# MCU.net
KiCad netlist of a schematic drawn in Altium Designer
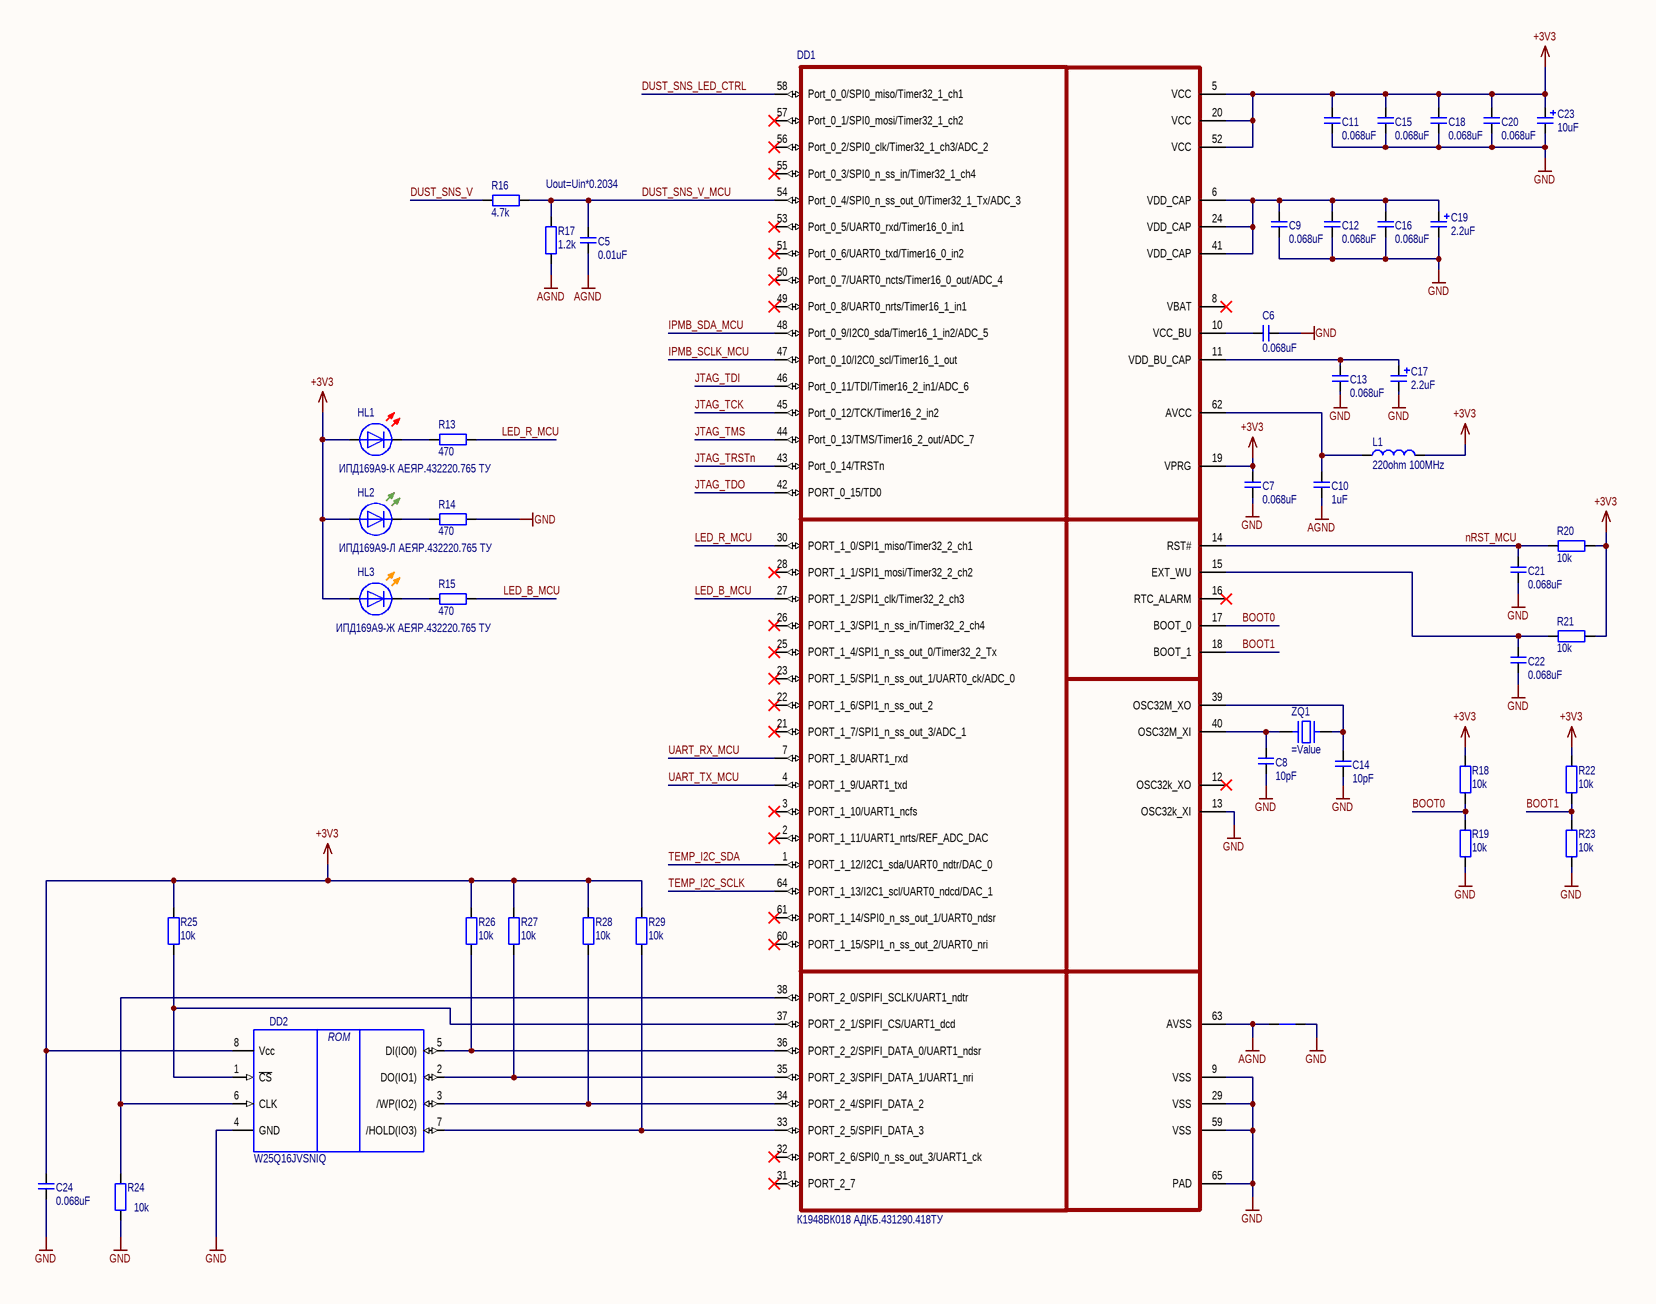
[diagram p0: MCU.SchDoc]

(export (version "E")
  (design (tool "Eeschema 10.0.6"))
  (components
    (comp (ref "C5")
      (value "0.01uF")
      (footprint "CAP 0603_1608")
      (description "Конденсатор К10-83 - 50 В - 0,01 мкФ ±20 % - Н20 - N - 1 АЖЯР.673511.008 ТУ")
      (fields
        (field (name "MANUFACTURER PART NUMBER") "К10-83 - 50 В - 0,01 мкФ ±20 % - Н20 - N - 1 АЖЯР.673511.008 ТУ")
        (field (name "TOLERANCE") "± 20%")
      )
      (libsource (lib "ComponentsDb") (part "Capacitor_Unpolar"))
    )
    (comp (ref "C6")
      (value "0.068uF")
      (footprint "CAP 0603_1608")
      (description "Конденсатор К10-83 - 10 В - 0,068 мкФ ±20 % - Н20 - N - 1 АЖЯР.673511.008 ТУ")
      (fields
        (field (name "MANUFACTURER PART NUMBER") "К10-83 - 10 В - 0,068 мкФ ±20 % - Н20 - N - 1 АЖЯР.673511.008 ТУ")
        (field (name "TOLERANCE") "± 20%")
      )
      (libsource (lib "ComponentsDb") (part "Capacitor_Unpolar"))
    )
    (comp (ref "C7")
      (value "0.068uF")
      (footprint "CAP 0603_1608")
      (description "Конденсатор К10-83 - 10 В - 0,068 мкФ ±20 % - Н20 - N - 1 АЖЯР.673511.008 ТУ")
      (fields
        (field (name "MANUFACTURER PART NUMBER") "К10-83 - 10 В - 0,068 мкФ ±20 % - Н20 - N - 1 АЖЯР.673511.008 ТУ")
        (field (name "TOLERANCE") "± 20%")
      )
      (libsource (lib "ComponentsDb") (part "Capacitor_Unpolar"))
    )
    (comp (ref "C8")
      (value "10pF")
      (footprint "CAP 0603_1608")
      (description "Конденсатор К10-83 - 50 В - 10 пФ ±10 % - МП0 - N - 1 АЖЯР.673511.008 ТУ")
      (fields
        (field (name "MANUFACTURER PART NUMBER") "К10-83 - 50 В - 10 пФ ±10 % - МП0 - N - 1 АЖЯР.673511.008 ТУ")
        (field (name "TOLERANCE") "± 10%")
      )
      (libsource (lib "ComponentsDb") (part "Capacitor_Unpolar"))
    )
    (comp (ref "C9")
      (value "0.068uF")
      (footprint "CAP 0603_1608")
      (description "Конденсатор К10-83 - 10 В - 0,068 мкФ ±20 % - Н20 - N - 1 АЖЯР.673511.008 ТУ")
      (fields
        (field (name "MANUFACTURER PART NUMBER") "К10-83 - 10 В - 0,068 мкФ ±20 % - Н20 - N - 1 АЖЯР.673511.008 ТУ")
        (field (name "TOLERANCE") "± 20%")
      )
      (libsource (lib "ComponentsDb") (part "Capacitor_Unpolar"))
    )
    (comp (ref "C10")
      (value "1uF")
      (footprint "CAP 1210_3225 - 1.8MM")
      (description "Конденсатор К10-83 - 16 В - 1 мкФ ±20 % - Н20 - N - 1 АЖЯР.673511.008 ТУ")
      (fields
        (field (name "MANUFACTURER PART NUMBER") "К10-83 - 16 В - 1 мкФ ±20 % - Н20 - N - 1 АЖЯР.673511.008 ТУ")
        (field (name "TOLERANCE") "± 20%")
      )
      (libsource (lib "ComponentsDb") (part "Capacitor_Unpolar"))
    )
    (comp (ref "C11")
      (value "0.068uF")
      (footprint "CAP 0603_1608")
      (description "Конденсатор К10-83 - 10 В - 0,068 мкФ ±20 % - Н20 - N - 1 АЖЯР.673511.008 ТУ")
      (fields
        (field (name "MANUFACTURER PART NUMBER") "К10-83 - 10 В - 0,068 мкФ ±20 % - Н20 - N - 1 АЖЯР.673511.008 ТУ")
        (field (name "TOLERANCE") "± 20%")
      )
      (libsource (lib "") (part "Capacitor_Unpolar_1"))
    )
    (comp (ref "C12")
      (value "0.068uF")
      (footprint "CAP 0603_1608")
      (description "Конденсатор К10-83 - 10 В - 0,068 мкФ ±20 % - Н20 - N - 1 АЖЯР.673511.008 ТУ")
      (fields
        (field (name "MANUFACTURER PART NUMBER") "К10-83 - 10 В - 0,068 мкФ ±20 % - Н20 - N - 1 АЖЯР.673511.008 ТУ")
        (field (name "TOLERANCE") "± 20%")
      )
      (libsource (lib "ComponentsDb") (part "Capacitor_Unpolar"))
    )
    (comp (ref "C13")
      (value "0.068uF")
      (footprint "CAP 0603_1608")
      (description "Конденсатор К10-83 - 10 В - 0,068 мкФ ±20 % - Н20 - N - 1 АЖЯР.673511.008 ТУ")
      (fields
        (field (name "MANUFACTURER PART NUMBER") "К10-83 - 10 В - 0,068 мкФ ±20 % - Н20 - N - 1 АЖЯР.673511.008 ТУ")
        (field (name "TOLERANCE") "± 20%")
      )
      (libsource (lib "ComponentsDb") (part "Capacitor_Unpolar"))
    )
    (comp (ref "C14")
      (value "10pF")
      (footprint "CAP 0603_1608")
      (description "Конденсатор К10-83 - 50 В - 10 пФ ±10 % - МП0 - N - 1 АЖЯР.673511.008 ТУ")
      (fields
        (field (name "MANUFACTURER PART NUMBER") "К10-83 - 50 В - 10 пФ ±10 % - МП0 - N - 1 АЖЯР.673511.008 ТУ")
        (field (name "TOLERANCE") "± 10%")
      )
      (libsource (lib "ComponentsDb") (part "Capacitor_Unpolar"))
    )
    (comp (ref "C15")
      (value "0.068uF")
      (footprint "CAP 0603_1608")
      (description "Конденсатор К10-83 - 10 В - 0,068 мкФ ±20 % - Н20 - N - 1 АЖЯР.673511.008 ТУ")
      (fields
        (field (name "MANUFACTURER PART NUMBER") "К10-83 - 10 В - 0,068 мкФ ±20 % - Н20 - N - 1 АЖЯР.673511.008 ТУ")
        (field (name "TOLERANCE") "± 20%")
      )
      (libsource (lib "") (part "Capacitor_Unpolar_1"))
    )
    (comp (ref "C16")
      (value "0.068uF")
      (footprint "CAP 0603_1608")
      (description "Конденсатор К10-83 - 10 В - 0,068 мкФ ±20 % - Н20 - N - 1 АЖЯР.673511.008 ТУ")
      (fields
        (field (name "MANUFACTURER PART NUMBER") "К10-83 - 10 В - 0,068 мкФ ±20 % - Н20 - N - 1 АЖЯР.673511.008 ТУ")
        (field (name "TOLERANCE") "± 20%")
      )
      (libsource (lib "ComponentsDb") (part "Capacitor_Unpolar"))
    )
    (comp (ref "C17")
      (value "2.2uF")
      (footprint "CAP ALSMD ELEC 4.3MM H5.4MM")
      (description "Конденсатор К50-97 – 50В – 2,2мкФ (±20) % – ЕВАЯ.673541.054ТУ")
      (fields
        (field (name "MANUFACTURER PART NUMBER") "К50-97 – 50В – 2,2мкФ (±20) % – ЕВАЯ.673541.054ТУ")
        (field (name "TOLERANCE") "± 20%")
      )
      (libsource (lib "ComponentsDb") (part "Capacitor_Polar"))
    )
    (comp (ref "C18")
      (value "0.068uF")
      (footprint "CAP 0603_1608")
      (description "Конденсатор К10-83 - 10 В - 0,068 мкФ ±20 % - Н20 - N - 1 АЖЯР.673511.008 ТУ")
      (fields
        (field (name "MANUFACTURER PART NUMBER") "К10-83 - 10 В - 0,068 мкФ ±20 % - Н20 - N - 1 АЖЯР.673511.008 ТУ")
        (field (name "TOLERANCE") "± 20%")
      )
      (libsource (lib "") (part "Capacitor_Unpolar_1"))
    )
    (comp (ref "C19")
      (value "2.2uF")
      (footprint "CAP ALSMD ELEC 4.3MM H5.4MM")
      (description "Конденсатор К50-97 – 50В – 2,2мкФ (±20) % – ЕВАЯ.673541.054ТУ")
      (fields
        (field (name "MANUFACTURER PART NUMBER") "К50-97 – 50В – 2,2мкФ (±20) % – ЕВАЯ.673541.054ТУ")
        (field (name "TOLERANCE") "± 20%")
      )
      (libsource (lib "ComponentsDb") (part "Capacitor_Polar"))
    )
    (comp (ref "C20")
      (value "0.068uF")
      (footprint "CAP 0603_1608")
      (description "Конденсатор К10-83 - 10 В - 0,068 мкФ ±20 % - Н20 - N - 1 АЖЯР.673511.008 ТУ")
      (fields
        (field (name "MANUFACTURER PART NUMBER") "К10-83 - 10 В - 0,068 мкФ ±20 % - Н20 - N - 1 АЖЯР.673511.008 ТУ")
        (field (name "TOLERANCE") "± 20%")
      )
      (libsource (lib "") (part "Capacitor_Unpolar_1"))
    )
    (comp (ref "C21")
      (value "0.068uF")
      (footprint "CAP 0603_1608")
      (description "Конденсатор К10-83 - 10 В - 0,068 мкФ ±20 % - Н20 - N - 1 АЖЯР.673511.008 ТУ")
      (fields
        (field (name "MANUFACTURER PART NUMBER") "К10-83 - 10 В - 0,068 мкФ ±20 % - Н20 - N - 1 АЖЯР.673511.008 ТУ")
        (field (name "TOLERANCE") "± 20%")
      )
      (libsource (lib "ComponentsDb") (part "Capacitor_Unpolar"))
    )
    (comp (ref "C22")
      (value "0.068uF")
      (footprint "CAP 0603_1608")
      (description "Конденсатор К10-83 - 10 В - 0,068 мкФ ±20 % - Н20 - N - 1 АЖЯР.673511.008 ТУ")
      (fields
        (field (name "MANUFACTURER PART NUMBER") "К10-83 - 10 В - 0,068 мкФ ±20 % - Н20 - N - 1 АЖЯР.673511.008 ТУ")
        (field (name "TOLERANCE") "± 20%")
      )
      (libsource (lib "ComponentsDb") (part "Capacitor_Unpolar"))
    )
    (comp (ref "C23")
      (value "10uF")
      (footprint "CAP ALSMD ELEC 4.3MM H5.4MM")
      (description "Конденсатор К50-97 – 25В – 10мкФ (±20) % – ЕВАЯ.673541.054ТУ")
      (fields
        (field (name "MANUFACTURER PART NUMBER") "К50-97 – 25В – 10мкФ (±20) % – ЕВАЯ.673541.054ТУ")
        (field (name "TOLERANCE") "± 20%")
      )
      (libsource (lib "ComponentsDb") (part "Capacitor_Polar"))
    )
    (comp (ref "C24")
      (value "0.068uF")
      (footprint "CAP 0603_1608")
      (description "Конденсатор К10-83 - 10 В - 0,068 мкФ ±20 % - Н20 АЖЯР.673511.008 ТУ")
      (fields
        (field (name "MANUFACTURER PART NUMBER") "К10-83 - 10 В - 0,068 мкФ ±20 % - Н20 АЖЯР.673511.008 ТУ")
        (field (name "TOLERANCE") "± 20%")
      )
      (libsource (lib "ComponentsDb") (part "Capacitor_Unpolar"))
    )
    (comp (ref "DD1")
      (value "К1948ВК018 АДКБ.431290.418ТУ")
      (footprint "QFN40P800X800X76_HS-65M")
      (description "Микроконтроллер К1948ВК018 АДКБ.431290.418ТУ")
      (fields (field (name "MANUFACTURER") "АО «МИКРОН»"))
      (libsource (lib "ComponentsDb") (part "К1948ВК018"))
    )
    (comp (ref "DD2")
      (value "W25Q16JVSNIQ")
      (footprint "WINBOND SOIC-8")
      (description "Память Flash W25Q16JVSNIQ")
      (fields (field (name "MANUFACTURER") "Winbond"))
      (libsource (lib "ComponentsDb") (part "W25Q16JVSNIQ"))
    )
    (comp (ref "HL1")
      (value "ИПД169А9-К АЕЯР.432220.765 ТУ")
      (footprint "LED 0603_1608 RED")
      (description "Индикатор ИПД169А9-К АЕЯР.432220.765 ТУ")
      (fields (field (name "MANUFACTURER") "АО «Протон»"))
      (libsource (lib "ComponentsDb") (part "LED_R_AC"))
    )
    (comp (ref "HL2")
      (value "ИПД169А9-Л АЕЯР.432220.765 ТУ")
      (footprint "LED 0603_1608 GREEN")
      (description "Индикатор ИПД169А9-Л АЕЯР.432220.765 ТУ")
      (fields (field (name "MANUFACTURER") "АО «Протон»"))
      (libsource (lib "ComponentsDb") (part "LED_G_AC"))
    )
    (comp (ref "HL3")
      (value "ИПД169А9-Ж АЕЯР.432220.765 ТУ")
      (footprint "LED 0603_1608 YELLOW")
      (description "Индикатор ИПД169А9-Ж АЕЯР.432220.765 ТУ")
      (fields (field (name "MANUFACTURER") "АО «Протон»"))
      (libsource (lib "ComponentsDb") (part "LED_Y_AC"))
    )
    (comp (ref "J1")
      (value "~")
      (footprint "NET_TIE_1MM")
      (description "Перемычка SMD NET_TIE_1MM")
      (fields (field (name "MANUFACTURER PART NUMBER") "NET_TIE_1MM"))
      (libsource (lib "ComponentsDb") (part "NetTie_2pin"))
    )
    (comp (ref "L1")
      (value "220ohm 100MHz")
      (footprint "FER 0805_2012")
      (description "Индуктивность ЭМП 0805-2A-220Ом ± 25% 100MHz")
      (fields (field (name "MANUFACTURER PART NUMBER") "BLM21PG221SN1D") (field (name "TOLERANCE") "±25%"))
      (libsource (lib "ComponentsDb") (part "Inductor"))
    )
    (comp (ref "R13")
      (value "470")
      (footprint "RES 0603_1608")
      (description "Резистор Р1-12 - 0,1 - 470Ом - ±1 % - У - \"А\" АЛЯР.434110.005 ТУ")
      (fields (field (name "TOLERANCE") "± 1%") (field (name "POWER") "0.1W"))
      (libsource (lib "ComponentsDb") (part "Resistor_b"))
    )
    (comp (ref "R14")
      (value "470")
      (footprint "RES 0603_1608")
      (description "Резистор Р1-12 - 0,1 - 470Ом - ±1 % - У - \"А\" АЛЯР.434110.005 ТУ")
      (fields (field (name "TOLERANCE") "± 1%") (field (name "POWER") "0.1W"))
      (libsource (lib "ComponentsDb") (part "Resistor_b"))
    )
    (comp (ref "R15")
      (value "470")
      (footprint "RES 0603_1608")
      (description "Резистор Р1-12 - 0,1 - 470Ом - ±1 % - У - \"А\" АЛЯР.434110.005 ТУ")
      (fields (field (name "TOLERANCE") "± 1%") (field (name "POWER") "0.1W"))
      (libsource (lib "ComponentsDb") (part "Resistor_b"))
    )
    (comp (ref "R16")
      (value "4.7k")
      (footprint "RES 0603_1608")
      (description "Резистор Р1-12 - 0,1 - 4,7кОм - ±1 % - У - \"А\" АЛЯР.434110.005 ТУ")
      (fields (field (name "TOLERANCE") "± 1%") (field (name "POWER") "0.1W"))
      (libsource (lib "ComponentsDb") (part "Resistor_b"))
    )
    (comp (ref "R17")
      (value "1.2k")
      (footprint "RES 0603_1608")
      (description "Резистор Р1-12 - 0,1 - 1,2кОм - ±1 % - У - \"А\" АЛЯР.434110.005 ТУ")
      (fields (field (name "TOLERANCE") "± 1%") (field (name "POWER") "0.1W"))
      (libsource (lib "ComponentsDb") (part "Resistor_b"))
    )
    (comp (ref "R18")
      (value "10k")
      (footprint "RES 0603_1608")
      (description "Резистор Р1-12 - 0,1 - 10кОм - ±1 % - У - \"А\" АЛЯР.434110.005 ТУ")
      (fields (field (name "TOLERANCE") "± 1%") (field (name "POWER") "0.1W"))
      (libsource (lib "ComponentsDb") (part "Resistor_b"))
    )
    (comp (ref "R19")
      (value "10k")
      (footprint "RES 0603_1608")
      (description "Резистор Р1-12 - 0,1 - 10кОм - ±1 % - У - \"А\" АЛЯР.434110.005 ТУ")
      (fields (field (name "TOLERANCE") "± 1%") (field (name "POWER") "0.1W"))
      (libsource (lib "ComponentsDb") (part "Resistor_b"))
    )
    (comp (ref "R20")
      (value "10k")
      (footprint "RES 0603_1608")
      (description "Резистор Р1-12 - 0,1 - 10кОм - ±1 % - У - \"А\" АЛЯР.434110.005 ТУ")
      (fields (field (name "TOLERANCE") "± 1%") (field (name "POWER") "0.1W"))
      (libsource (lib "ComponentsDb") (part "Resistor_b"))
    )
    (comp (ref "R21")
      (value "10k")
      (footprint "RES 0603_1608")
      (description "Резистор Р1-12 - 0,1 - 10кОм - ±1 % - У - \"А\" АЛЯР.434110.005 ТУ")
      (fields (field (name "TOLERANCE") "± 1%") (field (name "POWER") "0.1W"))
      (libsource (lib "ComponentsDb") (part "Resistor_b"))
    )
    (comp (ref "R22")
      (value "10k")
      (footprint "RES 0603_1608")
      (description "Резистор Р1-12 - 0,1 - 10кОм - ±1 % - У - \"А\" АЛЯР.434110.005 ТУ")
      (fields (field (name "TOLERANCE") "± 1%") (field (name "POWER") "0.1W"))
      (libsource (lib "ComponentsDb") (part "Resistor_b"))
    )
    (comp (ref "R23")
      (value "10k")
      (footprint "RES 0603_1608")
      (description "Резистор Р1-12 - 0,1 - 10кОм - ±1 % - У - \"А\" АЛЯР.434110.005 ТУ")
      (fields (field (name "TOLERANCE") "± 1%") (field (name "POWER") "0.1W"))
      (libsource (lib "ComponentsDb") (part "Resistor_b"))
    )
    (comp (ref "R24")
      (value "10k")
      (footprint "RES 0603_1608")
      (description "Резистор Р1-12 - 0,1 - 10кОм - ±1 % - У - \"А\" АЛЯР.434110.005 ТУ")
      (fields (field (name "TOLERANCE") "± 1%") (field (name "POWER") "0.1W"))
      (libsource (lib "ComponentsDb") (part "Resistor_b"))
    )
    (comp (ref "R25")
      (value "10k")
      (footprint "RES 0603_1608")
      (description "Резистор Р1-12 - 0,1 - 10кОм - ±1 % - У - \"А\" АЛЯР.434110.005 ТУ")
      (fields (field (name "TOLERANCE") "± 1%") (field (name "POWER") "0.1W"))
      (libsource (lib "ComponentsDb") (part "Resistor_b"))
    )
    (comp (ref "R26")
      (value "10k")
      (footprint "RES 0603_1608")
      (description "Резистор Р1-12 - 0,1 - 10кОм - ±1 % - У - \"А\" АЛЯР.434110.005 ТУ")
      (fields (field (name "TOLERANCE") "± 1%") (field (name "POWER") "0.1W"))
      (libsource (lib "ComponentsDb") (part "Resistor_b"))
    )
    (comp (ref "R27")
      (value "10k")
      (footprint "RES 0603_1608")
      (description "Резистор Р1-12 - 0,1 - 10кОм - ±1 % - У - \"А\" АЛЯР.434110.005 ТУ")
      (fields (field (name "TOLERANCE") "± 1%") (field (name "POWER") "0.1W"))
      (libsource (lib "ComponentsDb") (part "Resistor_b"))
    )
    (comp (ref "R28")
      (value "10k")
      (footprint "RES 0603_1608")
      (description "Резистор Р1-12 - 0,1 - 10кОм - ±1 % - У - \"А\" АЛЯР.434110.005 ТУ")
      (fields (field (name "TOLERANCE") "± 1%") (field (name "POWER") "0.1W"))
      (libsource (lib "ComponentsDb") (part "Resistor_b"))
    )
    (comp (ref "R29")
      (value "10k")
      (footprint "RES 0603_1608")
      (description "Резистор Р1-12 - 0,1 - 10кОм - ±1 % - У - \"А\" АЛЯР.434110.005 ТУ")
      (fields (field (name "TOLERANCE") "± 1%") (field (name "POWER") "0.1W"))
      (libsource (lib "ComponentsDb") (part "Resistor_b"))
    )
    (comp (ref "ZQ1")
      (value "~")
      (footprint "XTAL3225X07N")
      (description "Резонатор кварцевый РК1009-7ВП-32000К-В  (10 пФ) КЖБД.433514.031 ТУ")
      (fields
        (field (name "MANUFACTURER PART NUMBER") "РК1009-7ВП-32000К-В  (10 пФ) КЖБД.433514.031 ТУ")
        (field (name "TOLERANCE") "±20 ppm")
      )
      (libsource (lib "ComponentsDb") (part "QuartzCrystal_13"))
    )
  )
  (nets
    (net (code "1") (name "+3V3") (class "Default")
      (node (ref "C11") (pin "2") (pinfunction "2_2") (pintype "passive"))
      (node (ref "C15") (pin "2") (pinfunction "2_2") (pintype "passive"))
      (node (ref "C18") (pin "2") (pinfunction "2_2") (pintype "passive"))
      (node (ref "C20") (pin "2") (pinfunction "2_2") (pintype "passive"))
      (node (ref "C23") (pin "1") (pinfunction "P_1") (pintype "passive"))
      (node (ref "C24") (pin "2") (pinfunction "2_2") (pintype "passive"))
      (node (ref "C7") (pin "2") (pinfunction "2_2") (pintype "passive"))
      (node (ref "DD1") (pin "19") (pinfunction "VPRG_19") (pintype "passive"))
      (node (ref "DD1") (pin "20") (pinfunction "VCC_20") (pintype "power_in"))
      (node (ref "DD1") (pin "5") (pinfunction "VCC_5") (pintype "power_in"))
      (node (ref "DD1") (pin "52") (pinfunction "VCC_52") (pintype "power_in"))
      (node (ref "DD2") (pin "8") (pinfunction "Vcc_8") (pintype "power_in"))
      (node (ref "HL1") (pin "1") (pinfunction "A_1") (pintype "passive"))
      (node (ref "HL2") (pin "1") (pinfunction "A_1") (pintype "passive"))
      (node (ref "HL3") (pin "1") (pinfunction "A_1") (pintype "passive"))
      (node (ref "L1") (pin "2") (pinfunction "N_2") (pintype "passive"))
      (node (ref "R18") (pin "2") (pinfunction "2_2") (pintype "passive"))
      (node (ref "R20") (pin "1") (pinfunction "1_1") (pintype "passive"))
      (node (ref "R21") (pin "1") (pinfunction "1_1") (pintype "passive"))
      (node (ref "R22") (pin "2") (pinfunction "2_2") (pintype "passive"))
      (node (ref "R25") (pin "1") (pinfunction "1_1") (pintype "passive"))
      (node (ref "R26") (pin "2") (pinfunction "2_2") (pintype "passive"))
      (node (ref "R27") (pin "2") (pinfunction "2_2") (pintype "passive"))
      (node (ref "R28") (pin "2") (pinfunction "2_2") (pintype "passive"))
      (node (ref "R29") (pin "2") (pinfunction "2_2") (pintype "passive"))
    )
    (net (code "2") (name "/BOOT0") (class "Default")
      (node (ref "DD1") (pin "17") (pinfunction "BOOT_0_17") (pintype "passive"))
      (node (ref "R18") (pin "1") (pinfunction "1_1") (pintype "passive"))
      (node (ref "R19") (pin "2") (pinfunction "2_2") (pintype "passive"))
    )
    (net (code "3") (name "/BOOT1") (class "Default")
      (node (ref "DD1") (pin "18") (pinfunction "BOOT_1_18") (pintype "passive"))
      (node (ref "R22") (pin "1") (pinfunction "1_1") (pintype "passive"))
      (node (ref "R23") (pin "2") (pinfunction "2_2") (pintype "passive"))
    )
    (net (code "4") (name "/DUST_SNS_LED_CTRL") (class "Default")
      (node (ref "DD1") (pin "58") (pinfunction "Port_0_0/SPI0_miso/Timer32_1_ch1_58") (pintype "bidirectional"))
    )
    (net (code "5") (name "/DUST_SNS_V") (class "Default")
      (node (ref "R16") (pin "1") (pinfunction "1_1") (pintype "passive"))
    )
    (net (code "6") (name "/DUST_SNS_V_MCU") (class "Default")
      (node (ref "C5") (pin "1") (pinfunction "1_1") (pintype "passive"))
      (node (ref "DD1") (pin "54") (pinfunction "Port_0_4/SPI0_n_ss_out_0/Timer32_1_Tx/ADC_3_54") (pintype "bidirectional"))
      (node (ref "R16") (pin "2") (pinfunction "2_2") (pintype "passive"))
      (node (ref "R17") (pin "2") (pinfunction "2_2") (pintype "passive"))
    )
    (net (code "7") (name "/IPMB_SCLK_MCU") (class "Default")
      (node (ref "DD1") (pin "47") (pinfunction "Port_0_10/I2C0_scl/Timer16_1_out_47") (pintype "bidirectional"))
    )
    (net (code "8") (name "/IPMB_SDA_MCU") (class "Default")
      (node (ref "DD1") (pin "48") (pinfunction "Port_0_9/I2C0_sda/Timer16_1_in2/ADC_5_48") (pintype "bidirectional"))
    )
    (net (code "9") (name "/JTAG_TCK") (class "Default")
      (node (ref "DD1") (pin "45") (pinfunction "Port_0_12/TCK/Timer16_2_in2_45") (pintype "bidirectional"))
    )
    (net (code "10") (name "/JTAG_TDI") (class "Default")
      (node (ref "DD1") (pin "46") (pinfunction "Port_0_11/TDI/Timer16_2_in1/ADC_6_46") (pintype "bidirectional"))
    )
    (net (code "11") (name "/JTAG_TDO") (class "Default")
      (node (ref "DD1") (pin "42") (pinfunction "PORT_0_15/TD0_42") (pintype "bidirectional"))
    )
    (net (code "12") (name "/JTAG_TMS") (class "Default")
      (node (ref "DD1") (pin "44") (pinfunction "Port_0_13/TMS/Timer16_2_out/ADC_7_44") (pintype "bidirectional"))
    )
    (net (code "13") (name "/JTAG_TRSTn") (class "Default")
      (node (ref "DD1") (pin "43") (pinfunction "Port_0_14/TRSTn_43") (pintype "bidirectional"))
    )
    (net (code "14") (name "/LED_B_MCU") (class "Default")
      (node (ref "DD1") (pin "27") (pinfunction "PORT_1_2/SPI1_clk/Timer32_2_ch3_27") (pintype "bidirectional"))
      (node (ref "R15") (pin "2") (pinfunction "2_2") (pintype "passive"))
    )
    (net (code "15") (name "/LED_R_MCU") (class "Default")
      (node (ref "DD1") (pin "30") (pinfunction "PORT_1_0/SPI1_miso/Timer32_2_ch1_30") (pintype "bidirectional"))
      (node (ref "R13") (pin "2") (pinfunction "2_2") (pintype "passive"))
    )
    (net (code "16") (name "/TEMP_I2C_SCLK") (class "Default")
      (node (ref "DD1") (pin "64") (pinfunction "PORT_1_13/I2C1_scl/UART0_ndcd/DAC_1_64") (pintype "bidirectional"))
    )
    (net (code "17") (name "/TEMP_I2C_SDA") (class "Default")
      (node (ref "DD1") (pin "1") (pinfunction "PORT_1_12/I2C1_sda/UART0_ndtr/DAC_0_1") (pintype "bidirectional"))
    )
    (net (code "18") (name "/UART_RX_MCU") (class "Default")
      (node (ref "DD1") (pin "7") (pinfunction "PORT_1_8/UART1_rxd_7") (pintype "bidirectional"))
    )
    (net (code "19") (name "/UART_TX_MCU") (class "Default")
      (node (ref "DD1") (pin "4") (pinfunction "PORT_1_9/UART1_txd_4") (pintype "bidirectional"))
    )
    (net (code "20") (name "/nRST_MCU") (class "Default")
      (node (ref "C21") (pin "2") (pinfunction "2_2") (pintype "passive"))
      (node (ref "DD1") (pin "14") (pinfunction "RST#_14") (pintype "passive"))
      (node (ref "R20") (pin "2") (pinfunction "2_2") (pintype "passive"))
    )
    (net (code "21") (name "AGND") (class "Default")
      (node (ref "C10") (pin "1") (pinfunction "1_1") (pintype "passive"))
      (node (ref "C5") (pin "2") (pinfunction "2_2") (pintype "passive"))
      (node (ref "DD1") (pin "63") (pinfunction "AVSS_63") (pintype "power_in"))
      (node (ref "J1") (pin "1") (pinfunction "P_1") (pintype "passive"))
      (node (ref "R17") (pin "1") (pinfunction "1_1") (pintype "passive"))
    )
    (net (code "22") (name "GND") (class "Default")
      (node (ref "C11") (pin "1") (pinfunction "1_1") (pintype "passive"))
      (node (ref "C12") (pin "1") (pinfunction "1_1") (pintype "passive"))
      (node (ref "C13") (pin "1") (pinfunction "1_1") (pintype "passive"))
      (node (ref "C14") (pin "1") (pinfunction "1_1") (pintype "passive"))
      (node (ref "C15") (pin "1") (pinfunction "1_1") (pintype "passive"))
      (node (ref "C16") (pin "1") (pinfunction "1_1") (pintype "passive"))
      (node (ref "C17") (pin "2") (pinfunction "N_2") (pintype "passive"))
      (node (ref "C18") (pin "1") (pinfunction "1_1") (pintype "passive"))
      (node (ref "C19") (pin "2") (pinfunction "N_2") (pintype "passive"))
      (node (ref "C20") (pin "1") (pinfunction "1_1") (pintype "passive"))
      (node (ref "C21") (pin "1") (pinfunction "1_1") (pintype "passive"))
      (node (ref "C22") (pin "1") (pinfunction "1_1") (pintype "passive"))
      (node (ref "C23") (pin "2") (pinfunction "N_2") (pintype "passive"))
      (node (ref "C24") (pin "1") (pinfunction "1_1") (pintype "passive"))
      (node (ref "C6") (pin "1") (pinfunction "1_1") (pintype "passive"))
      (node (ref "C7") (pin "1") (pinfunction "1_1") (pintype "passive"))
      (node (ref "C8") (pin "1") (pinfunction "1_1") (pintype "passive"))
      (node (ref "C9") (pin "1") (pinfunction "1_1") (pintype "passive"))
      (node (ref "DD1") (pin "13") (pinfunction "OSC32k_XI_13") (pintype "passive"))
      (node (ref "DD1") (pin "29") (pinfunction "VSS_29") (pintype "power_in"))
      (node (ref "DD1") (pin "59") (pinfunction "VSS_59") (pintype "power_in"))
      (node (ref "DD1") (pin "65") (pinfunction "PAD_65") (pintype "power_in"))
      (node (ref "DD1") (pin "9") (pinfunction "VSS_9") (pintype "power_in"))
      (node (ref "DD2") (pin "4") (pinfunction "GND_4") (pintype "passive"))
      (node (ref "J1") (pin "2") (pinfunction "N_2") (pintype "passive"))
      (node (ref "R14") (pin "2") (pinfunction "2_2") (pintype "passive"))
      (node (ref "R19") (pin "1") (pinfunction "1_1") (pintype "passive"))
      (node (ref "R23") (pin "1") (pinfunction "1_1") (pintype "passive"))
      (node (ref "R24") (pin "1") (pinfunction "1_1") (pintype "passive"))
    )
    (net (code "23") (name "Net-(C17-P)") (class "Default")
      (node (ref "C13") (pin "2") (pinfunction "2_2") (pintype "passive"))
      (node (ref "C17") (pin "1") (pinfunction "P_1") (pintype "passive"))
      (node (ref "DD1") (pin "11") (pinfunction "VDD_BU_CAP_11") (pintype "passive"))
    )
    (net (code "24") (name "Net-(C19-P)") (class "Default")
      (node (ref "C12") (pin "2") (pinfunction "2_2") (pintype "passive"))
      (node (ref "C16") (pin "2") (pinfunction "2_2") (pintype "passive"))
      (node (ref "C19") (pin "1") (pinfunction "P_1") (pintype "passive"))
      (node (ref "C9") (pin "2") (pinfunction "2_2") (pintype "passive"))
      (node (ref "DD1") (pin "24") (pinfunction "VDD_CAP_24") (pintype "passive"))
      (node (ref "DD1") (pin "41") (pinfunction "VDD_CAP_41") (pintype "passive"))
      (node (ref "DD1") (pin "6") (pinfunction "VDD_CAP_6") (pintype "passive"))
    )
    (net (code "25") (name "Net-(DD1-AVCC)") (class "Default")
      (node (ref "C10") (pin "2") (pinfunction "2_2") (pintype "passive"))
      (node (ref "DD1") (pin "62") (pinfunction "AVCC_62") (pintype "power_in"))
      (node (ref "L1") (pin "1") (pinfunction "P_1") (pintype "passive"))
    )
    (net (code "26") (name "Net-(DD1-EXT_WU)") (class "Default")
      (node (ref "C22") (pin "2") (pinfunction "2_2") (pintype "passive"))
      (node (ref "DD1") (pin "15") (pinfunction "EXT_WU_15") (pintype "passive"))
      (node (ref "R21") (pin "2") (pinfunction "2_2") (pintype "passive"))
    )
    (net (code "27") (name "Net-(DD1-OSC32M_XI)") (class "Default")
      (node (ref "C8") (pin "2") (pinfunction "2_2") (pintype "passive"))
      (node (ref "DD1") (pin "40") (pinfunction "OSC32M_XI_40") (pintype "passive"))
      (node (ref "ZQ1") (pin "1") (pinfunction "1_1") (pintype "passive"))
    )
    (net (code "28") (name "Net-(DD1-OSC32M_XO)") (class "Default")
      (node (ref "C14") (pin "2") (pinfunction "2_2") (pintype "passive"))
      (node (ref "DD1") (pin "39") (pinfunction "OSC32M_XO_39") (pintype "passive"))
      (node (ref "ZQ1") (pin "3") (pinfunction "3_3") (pintype "passive"))
    )
    (net (code "29") (name "Net-(DD1-PORT_2_0{slash}SPIFI_SCLK{slash}UART1_ndtr)") (class "Default")
      (node (ref "DD1") (pin "38") (pinfunction "PORT_2_0/SPIFI_SCLK/UART1_ndtr_38") (pintype "bidirectional"))
      (node (ref "DD2") (pin "6") (pinfunction "CLK_6") (pintype "input"))
      (node (ref "R24") (pin "2") (pinfunction "2_2") (pintype "passive"))
    )
    (net (code "30") (name "Net-(DD1-PORT_2_1{slash}SPIFI_CS{slash}UART1_dcd)") (class "Default")
      (node (ref "DD1") (pin "37") (pinfunction "PORT_2_1/SPIFI_CS/UART1_dcd_37") (pintype "bidirectional"))
      (node (ref "DD2") (pin "1") (pinfunction "CS_1") (pintype "input"))
      (node (ref "R25") (pin "2") (pinfunction "2_2") (pintype "passive"))
    )
    (net (code "31") (name "Net-(DD1-PORT_2_2{slash}SPIFI_DATA_0{slash}UART1_ndsr)") (class "Default")
      (node (ref "DD1") (pin "36") (pinfunction "PORT_2_2/SPIFI_DATA_0/UART1_ndsr_36") (pintype "bidirectional"))
      (node (ref "DD2") (pin "5") (pinfunction "DI(IO0)_5") (pintype "bidirectional"))
      (node (ref "R26") (pin "1") (pinfunction "1_1") (pintype "passive"))
    )
    (net (code "32") (name "Net-(DD1-PORT_2_3{slash}SPIFI_DATA_1{slash}UART1_nri)") (class "Default")
      (node (ref "DD1") (pin "35") (pinfunction "PORT_2_3/SPIFI_DATA_1/UART1_nri_35") (pintype "bidirectional"))
      (node (ref "DD2") (pin "2") (pinfunction "DO(IO1)_2") (pintype "bidirectional"))
      (node (ref "R27") (pin "1") (pinfunction "1_1") (pintype "passive"))
    )
    (net (code "33") (name "Net-(DD1-PORT_2_4{slash}SPIFI_DATA_2)") (class "Default")
      (node (ref "DD1") (pin "34") (pinfunction "PORT_2_4/SPIFI_DATA_2_34") (pintype "bidirectional"))
      (node (ref "DD2") (pin "3") (pinfunction "/WP(IO2)_3") (pintype "bidirectional"))
      (node (ref "R28") (pin "1") (pinfunction "1_1") (pintype "passive"))
    )
    (net (code "34") (name "Net-(DD1-PORT_2_5{slash}SPIFI_DATA_3)") (class "Default")
      (node (ref "DD1") (pin "33") (pinfunction "PORT_2_5/SPIFI_DATA_3_33") (pintype "bidirectional"))
      (node (ref "DD2") (pin "7") (pinfunction "/HOLD(IO3)_7") (pintype "bidirectional"))
      (node (ref "R29") (pin "1") (pinfunction "1_1") (pintype "passive"))
    )
    (net (code "35") (name "Net-(DD1-VCC_BU)") (class "Default")
      (node (ref "C6") (pin "2") (pinfunction "2_2") (pintype "passive"))
      (node (ref "DD1") (pin "10") (pinfunction "VCC_BU_10") (pintype "passive"))
    )
    (net (code "36") (name "Net-(HL1-C)") (class "Default")
      (node (ref "HL1") (pin "2") (pinfunction "C_2") (pintype "passive"))
      (node (ref "R13") (pin "1") (pinfunction "1_1") (pintype "passive"))
    )
    (net (code "37") (name "Net-(HL2-C)") (class "Default")
      (node (ref "HL2") (pin "2") (pinfunction "C_2") (pintype "passive"))
      (node (ref "R14") (pin "1") (pinfunction "1_1") (pintype "passive"))
    )
    (net (code "38") (name "Net-(HL3-C)") (class "Default")
      (node (ref "HL3") (pin "2") (pinfunction "C_2") (pintype "passive"))
      (node (ref "R15") (pin "1") (pinfunction "1_1") (pintype "passive"))
    )
    (net (code "39") (name "unconnected-(DD1-OSC32k_XO-Pad12)") (class "Default")
      (node (ref "DD1") (pin "12") (pinfunction "OSC32k_XO_12") (pintype "passive+no_connect"))
    )
    (net (code "40") (name "unconnected-(DD1-PORT_1_1{slash}SPI1_mosi{slash}Timer32_2_ch2-Pad28)") (class "Default")
      (node (ref "DD1") (pin "28") (pinfunction "PORT_1_1/SPI1_mosi/Timer32_2_ch2_28") (pintype "bidirectional+no_connect"))
    )
    (net (code "41") (name "unconnected-(DD1-PORT_1_3{slash}SPI1_n_ss_in{slash}Timer32_2_ch4-Pad26)") (class "Default")
      (node (ref "DD1") (pin "26") (pinfunction "PORT_1_3/SPI1_n_ss_in/Timer32_2_ch4_26") (pintype "bidirectional+no_connect"))
    )
    (net (code "42") (name "unconnected-(DD1-PORT_1_4{slash}SPI1_n_ss_out_0{slash}Timer32_2_Tx-Pad25)") (class "Default")
      (node (ref "DD1") (pin "25") (pinfunction "PORT_1_4/SPI1_n_ss_out_0/Timer32_2_Tx_25") (pintype "bidirectional+no_connect"))
    )
    (net (code "43") (name "unconnected-(DD1-PORT_1_5{slash}SPI1_n_ss_out_1{slash}UART0_ck{slash}ADC_0-Pad23)") (class "Default")
      (node (ref "DD1") (pin "23") (pinfunction "PORT_1_5/SPI1_n_ss_out_1/UART0_ck/ADC_0_23") (pintype "bidirectional+no_connect"))
    )
    (net (code "44") (name "unconnected-(DD1-PORT_1_6{slash}SPI1_n_ss_out_2-Pad22)") (class "Default")
      (node (ref "DD1") (pin "22") (pinfunction "PORT_1_6/SPI1_n_ss_out_2_22") (pintype "bidirectional+no_connect"))
    )
    (net (code "45") (name "unconnected-(DD1-PORT_1_7{slash}SPI1_n_ss_out_3{slash}ADC_1-Pad21)") (class "Default")
      (node (ref "DD1") (pin "21") (pinfunction "PORT_1_7/SPI1_n_ss_out_3/ADC_1_21") (pintype "bidirectional+no_connect"))
    )
    (net (code "46") (name "unconnected-(DD1-PORT_1_10{slash}UART1_ncfs-Pad3)") (class "Default")
      (node (ref "DD1") (pin "3") (pinfunction "PORT_1_10/UART1_ncfs_3") (pintype "bidirectional+no_connect"))
    )
    (net (code "47") (name "unconnected-(DD1-PORT_1_11{slash}UART1_nrts{slash}REF_ADC_DAC-Pad2)") (class "Default")
      (node (ref "DD1") (pin "2") (pinfunction "PORT_1_11/UART1_nrts/REF_ADC_DAC_2") (pintype "bidirectional+no_connect"))
    )
    (net (code "48") (name "unconnected-(DD1-PORT_1_14{slash}SPI0_n_ss_out_1{slash}UART0_ndsr-Pad61)") (class "Default")
      (node (ref "DD1") (pin "61") (pinfunction "PORT_1_14/SPI0_n_ss_out_1/UART0_ndsr_61") (pintype "bidirectional+no_connect"))
    )
    (net (code "49") (name "unconnected-(DD1-PORT_1_15{slash}SPI1_n_ss_out_2{slash}UART0_nri-Pad60)") (class "Default")
      (node (ref "DD1") (pin "60") (pinfunction "PORT_1_15/SPI1_n_ss_out_2/UART0_nri_60") (pintype "bidirectional+no_connect"))
    )
    (net (code "50") (name "unconnected-(DD1-PORT_2_6{slash}SPI0_n_ss_out_3{slash}UART1_ck-Pad32)") (class "Default")
      (node (ref "DD1") (pin "32") (pinfunction "PORT_2_6/SPI0_n_ss_out_3/UART1_ck_32") (pintype "bidirectional+no_connect"))
    )
    (net (code "51") (name "unconnected-(DD1-PORT_2_7-Pad31)") (class "Default")
      (node (ref "DD1") (pin "31") (pinfunction "PORT_2_7_31") (pintype "bidirectional+no_connect"))
    )
    (net (code "52") (name "unconnected-(DD1-Port_0_1{slash}SPI0_mosi{slash}Timer32_1_ch2-Pad57)") (class "Default")
      (node (ref "DD1") (pin "57") (pinfunction "Port_0_1/SPI0_mosi/Timer32_1_ch2_57") (pintype "bidirectional+no_connect"))
    )
    (net (code "53") (name "unconnected-(DD1-Port_0_2{slash}SPI0_clk{slash}Timer32_1_ch3{slash}ADC_2-Pad56)") (class "Default")
      (node (ref "DD1") (pin "56") (pinfunction "Port_0_2/SPI0_clk/Timer32_1_ch3/ADC_2_56") (pintype "bidirectional+no_connect"))
    )
    (net (code "54") (name "unconnected-(DD1-Port_0_3{slash}SPI0_n_ss_in{slash}Timer32_1_ch4-Pad55)") (class "Default")
      (node (ref "DD1") (pin "55") (pinfunction "Port_0_3/SPI0_n_ss_in/Timer32_1_ch4_55") (pintype "bidirectional+no_connect"))
    )
    (net (code "55") (name "unconnected-(DD1-Port_0_5{slash}UART0_rxd{slash}Timer16_0_in1-Pad53)") (class "Default")
      (node (ref "DD1") (pin "53") (pinfunction "Port_0_5/UART0_rxd/Timer16_0_in1_53") (pintype "bidirectional+no_connect"))
    )
    (net (code "56") (name "unconnected-(DD1-Port_0_6{slash}UART0_txd{slash}Timer16_0_in2-Pad51)") (class "Default")
      (node (ref "DD1") (pin "51") (pinfunction "Port_0_6/UART0_txd/Timer16_0_in2_51") (pintype "bidirectional+no_connect"))
    )
    (net (code "57") (name "unconnected-(DD1-Port_0_7{slash}UART0_ncts{slash}Timer16_0_out{slash}ADC_4-Pad50)") (class "Default")
      (node (ref "DD1") (pin "50") (pinfunction "Port_0_7/UART0_ncts/Timer16_0_out/ADC_4_50") (pintype "bidirectional+no_connect"))
    )
    (net (code "58") (name "unconnected-(DD1-Port_0_8{slash}UART0_nrts{slash}Timer16_1_in1-Pad49)") (class "Default")
      (node (ref "DD1") (pin "49") (pinfunction "Port_0_8/UART0_nrts/Timer16_1_in1_49") (pintype "bidirectional+no_connect"))
    )
    (net (code "59") (name "unconnected-(DD1-RTC_ALARM-Pad16)") (class "Default")
      (node (ref "DD1") (pin "16") (pinfunction "RTC_ALARM_16") (pintype "passive+no_connect"))
    )
    (net (code "60") (name "unconnected-(DD1-VBAT-Pad8)") (class "Default")
      (node (ref "DD1") (pin "8") (pinfunction "VBAT_8") (pintype "passive+no_connect"))
    )
  )
)
